# DCDC-5V5V3A.net
KiCad netlist of a schematic drawn in EAGLE
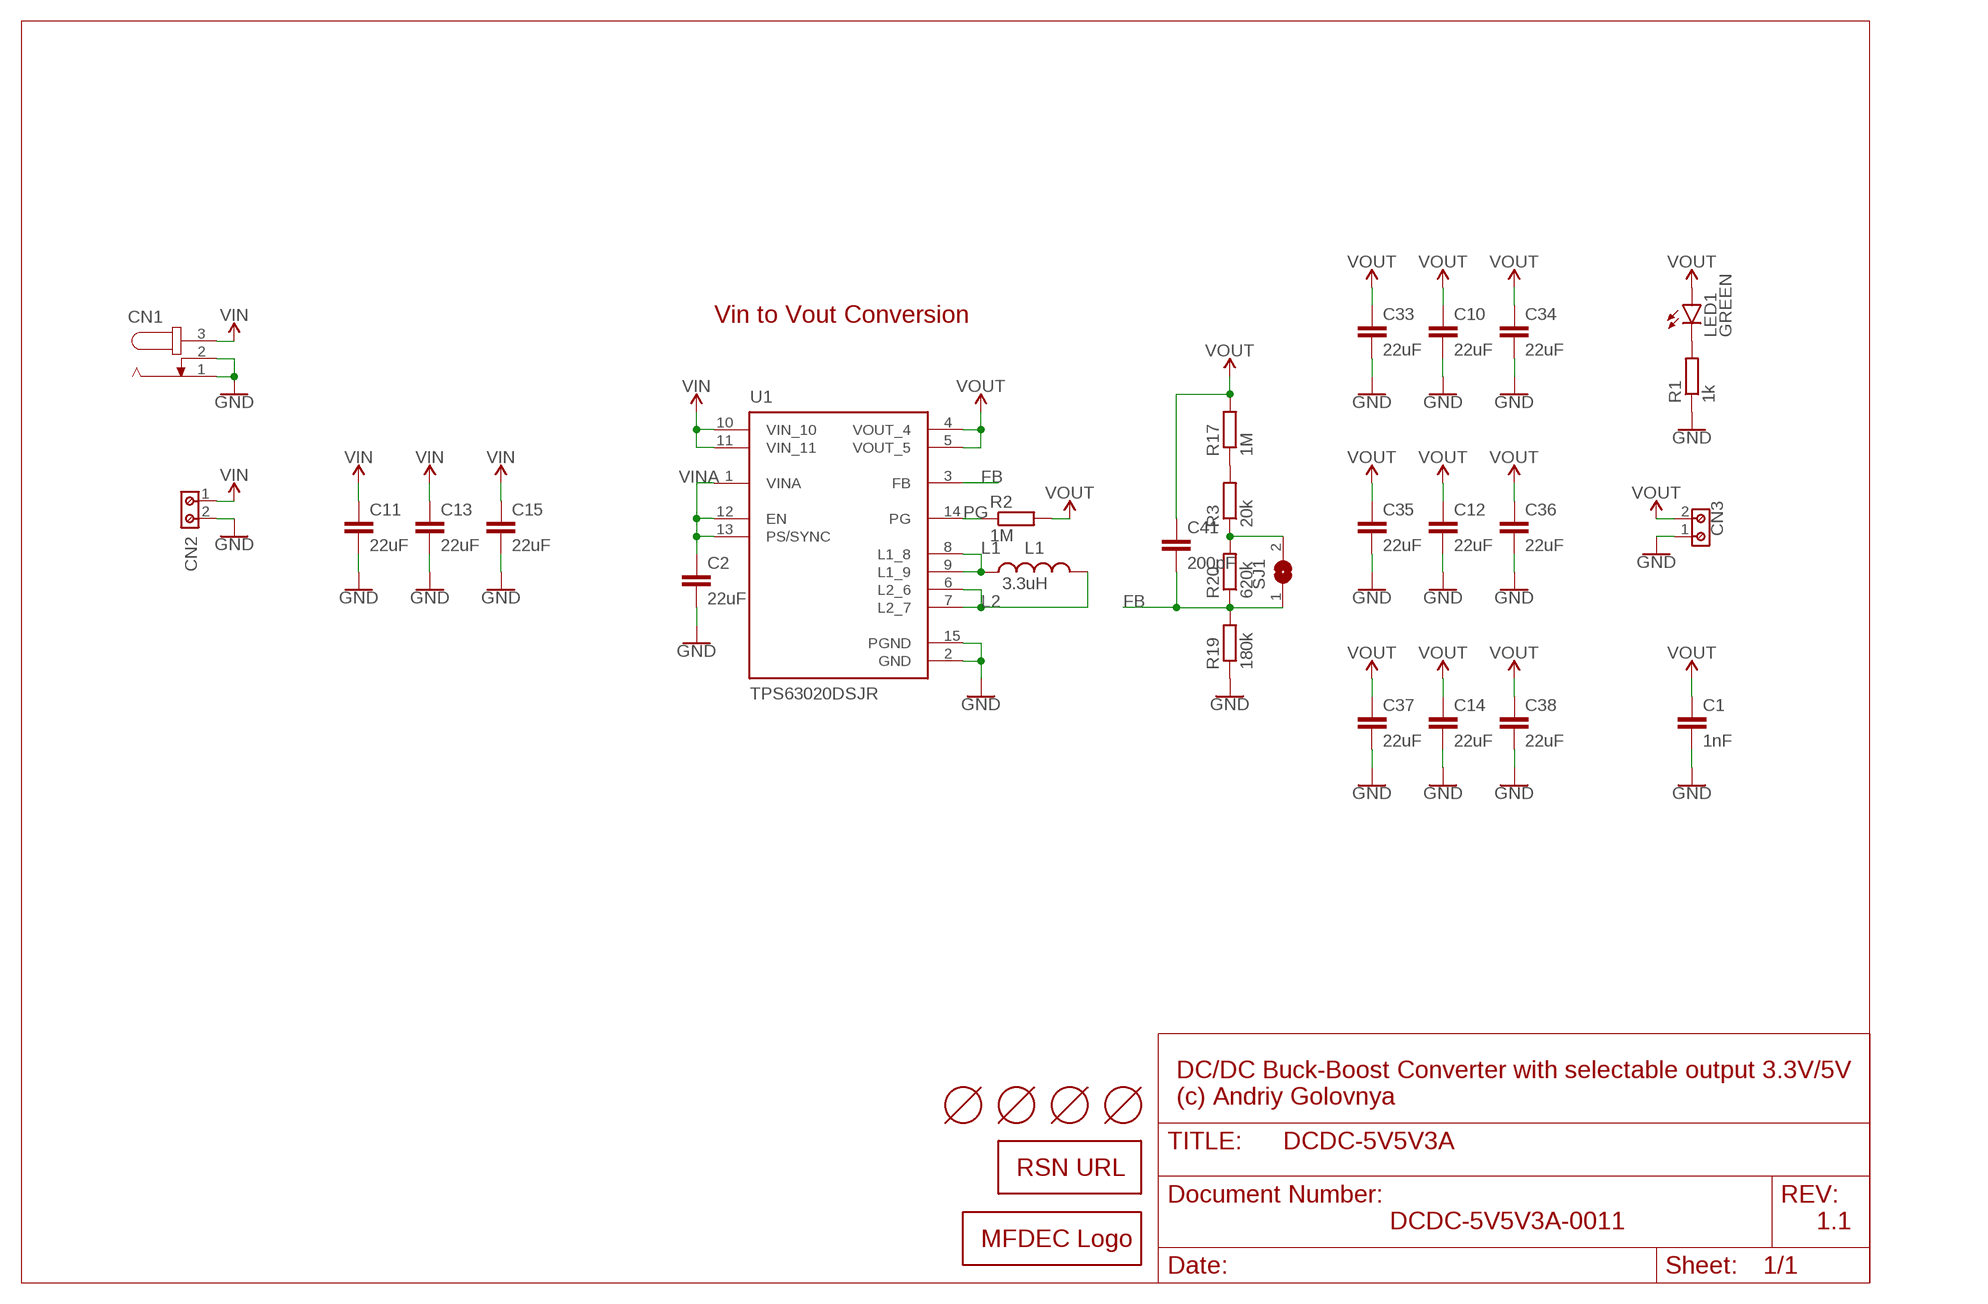
[diagram p0: schematic, sheet 1]

(export (version "E")
  (design (tool "Eeschema 10.0.6"))
  (components
    (comp (ref "C1")
      (value "1nF")
      (footprint "eagle-import:C0603K")
      (libsource (lib "eagle-import") (part "C-EUC0603K"))
    )
    (comp (ref "C2")
      (value "22uF")
      (footprint "eagle-import:C0805K")
      (libsource (lib "eagle-import") (part "C-EUC0805K"))
    )
    (comp (ref "C10")
      (value "22uF")
      (footprint "eagle-import:C0805K")
      (libsource (lib "eagle-import") (part "C-EUC0805K"))
    )
    (comp (ref "C11")
      (value "22uF")
      (footprint "eagle-import:C0805K")
      (libsource (lib "eagle-import") (part "C-EUC0805K"))
    )
    (comp (ref "C12")
      (value "22uF")
      (footprint "eagle-import:C0805K")
      (libsource (lib "eagle-import") (part "C-EUC0805K"))
    )
    (comp (ref "C13")
      (value "22uF")
      (footprint "eagle-import:C0805K")
      (libsource (lib "eagle-import") (part "C-EUC0805K"))
    )
    (comp (ref "C14")
      (value "22uF")
      (footprint "eagle-import:C0805K")
      (libsource (lib "eagle-import") (part "C-EUC0805K"))
    )
    (comp (ref "C15")
      (value "22uF")
      (footprint "eagle-import:C0805K")
      (libsource (lib "eagle-import") (part "C-EUC0805K"))
    )
    (comp (ref "C33")
      (value "22uF")
      (footprint "eagle-import:C0805K")
      (libsource (lib "eagle-import") (part "C-EUC0805K"))
    )
    (comp (ref "C34")
      (value "22uF")
      (footprint "eagle-import:C0805K")
      (libsource (lib "eagle-import") (part "C-EUC0805K"))
    )
    (comp (ref "C35")
      (value "22uF")
      (footprint "eagle-import:C0805K")
      (libsource (lib "eagle-import") (part "C-EUC0805K"))
    )
    (comp (ref "C36")
      (value "22uF")
      (footprint "eagle-import:C0805K")
      (libsource (lib "eagle-import") (part "C-EUC0805K"))
    )
    (comp (ref "C37")
      (value "22uF")
      (footprint "eagle-import:C0805K")
      (libsource (lib "eagle-import") (part "C-EUC0805K"))
    )
    (comp (ref "C38")
      (value "22uF")
      (footprint "eagle-import:C0805K")
      (libsource (lib "eagle-import") (part "C-EUC0805K"))
    )
    (comp (ref "C41")
      (value "200pF")
      (footprint "eagle-import:C0603K")
      (libsource (lib "eagle-import") (part "C-EUC0603K"))
    )
    (comp (ref "CN1")
      (value "JACK-PLUG1")
      (footprint "eagle-import:SPC4078")
      (libsource (lib "eagle-import") (part "JACK-PLUG1"))
    )
    (comp (ref "CN2")
      (value "691213510002")
      (footprint "eagle-import:691213510002")
      (libsource (lib "eagle-import") (part "691213510002"))
    )
    (comp (ref "CN3")
      (value "691213510002")
      (footprint "eagle-import:691213510002")
      (libsource (lib "eagle-import") (part "691213510002"))
    )
    (comp (ref "HOLE1")
      (value "TOOLINGHOLE")
      (footprint "eagle-import:TOOLING-HOLE")
      (libsource (lib "eagle-import") (part "TOOLINGHOLE"))
    )
    (comp (ref "HOLE2")
      (value "TOOLINGHOLE")
      (footprint "eagle-import:TOOLING-HOLE")
      (libsource (lib "eagle-import") (part "TOOLINGHOLE"))
    )
    (comp (ref "HOLE3")
      (value "TOOLINGHOLE")
      (footprint "eagle-import:TOOLING-HOLE")
      (libsource (lib "eagle-import") (part "TOOLINGHOLE"))
    )
    (comp (ref "HOLE4")
      (value "TOOLINGHOLE")
      (footprint "eagle-import:TOOLING-HOLE")
      (libsource (lib "eagle-import") (part "TOOLINGHOLE"))
    )
    (comp (ref "L1")
      (value "3.3uH")
      (footprint "eagle-import:WE-CHSA_1011")
      (libsource (lib "eagle-import") (part "WE-CHSA_1011_7843330330"))
    )
    (comp (ref "LED1")
      (value "GREEN")
      (footprint "eagle-import:SML0603")
      (libsource (lib "eagle-import") (part "LEDSML0603"))
    )
    (comp (ref "LOGO1")
      (value "RSNURL_QR_8MM")
      (footprint "eagle-import:RSNURL_QR_8MM")
      (libsource (lib "eagle-import") (part "RSNURL_QR_8MM"))
    )
    (comp (ref "LOGO2")
      (value "MFDECLOGO_L_10MM")
      (footprint "eagle-import:MFDEC_L_10MM")
      (libsource (lib "eagle-import") (part "MFDECLOGO_L_10MM"))
    )
    (comp (ref "R1")
      (value "1k")
      (footprint "eagle-import:R0603")
      (libsource (lib "eagle-import") (part "R-EU_R0603"))
    )
    (comp (ref "R2")
      (value "1M")
      (footprint "eagle-import:R0603")
      (libsource (lib "eagle-import") (part "R-EU_R0603"))
    )
    (comp (ref "R3")
      (value "20k")
      (footprint "eagle-import:R0603")
      (libsource (lib "eagle-import") (part "R-EU_R0603"))
    )
    (comp (ref "R17")
      (value "1M")
      (footprint "eagle-import:R0603")
      (libsource (lib "eagle-import") (part "R-EU_R0603"))
    )
    (comp (ref "R19")
      (value "180k")
      (footprint "eagle-import:R0603")
      (libsource (lib "eagle-import") (part "R-EU_R0603"))
    )
    (comp (ref "R20")
      (value "620k")
      (footprint "eagle-import:R0603")
      (libsource (lib "eagle-import") (part "R-EU_R0603"))
    )
    (comp (ref "SJ1") (value "SJ") (footprint "eagle-import:SJ") (libsource (lib "eagle-import") (part "SJ")))
    (comp (ref "U1")
      (value "TPS63020DSJR")
      (footprint "eagle-import:IC_TPS63020DSJR")
      (fields (field (name "MF") "Texas Instruments"))
      (libsource (lib "eagle-import") (part "TPS63020DSJR"))
    )
  )
  (nets
    (net (code "1") (name "/FB") (class "Default")
      (node (ref "C41") (pin "2") (pinfunction "2_2") (pintype "passive"))
      (node (ref "R19") (pin "2") (pinfunction "2_2") (pintype "passive"))
      (node (ref "R20") (pin "1") (pinfunction "1_1") (pintype "passive"))
      (node (ref "SJ1") (pin "1") (pinfunction "1_1") (pintype "passive"))
      (node (ref "U1") (pin "3") (pinfunction "FB_3") (pintype "input"))
    )
    (net (code "2") (name "/L1") (class "Default")
      (node (ref "L1") (pin "1") (pinfunction "1_1") (pintype "passive"))
      (node (ref "U1") (pin "8") (pinfunction "L1_8_8") (pintype "passive"))
      (node (ref "U1") (pin "9") (pinfunction "L1_9_9") (pintype "passive"))
    )
    (net (code "3") (name "/L2") (class "Default")
      (node (ref "L1") (pin "2") (pinfunction "2_2") (pintype "passive"))
      (node (ref "U1") (pin "6") (pinfunction "L2_6_6") (pintype "passive"))
      (node (ref "U1") (pin "7") (pinfunction "L2_7_7") (pintype "passive"))
    )
    (net (code "4") (name "/PG") (class "Default")
      (node (ref "R2") (pin "1") (pinfunction "1_1") (pintype "passive"))
      (node (ref "U1") (pin "14") (pinfunction "PG_14") (pintype "output"))
    )
    (net (code "5") (name "/VINA") (class "Default")
      (node (ref "C2") (pin "1") (pinfunction "1_1") (pintype "passive"))
      (node (ref "U1") (pin "1") (pinfunction "VINA_1") (pintype "input"))
      (node (ref "U1") (pin "12") (pinfunction "EN_12") (pintype "input"))
      (node (ref "U1") (pin "13") (pinfunction "PS/SYNC_13") (pintype "input"))
    )
    (net (code "6") (name "GND") (class "Default")
      (node (ref "C1") (pin "2") (pinfunction "2_2") (pintype "passive"))
      (node (ref "C10") (pin "2") (pinfunction "2_2") (pintype "passive"))
      (node (ref "C11") (pin "2") (pinfunction "2_2") (pintype "passive"))
      (node (ref "C12") (pin "2") (pinfunction "2_2") (pintype "passive"))
      (node (ref "C13") (pin "2") (pinfunction "2_2") (pintype "passive"))
      (node (ref "C14") (pin "2") (pinfunction "2_2") (pintype "passive"))
      (node (ref "C15") (pin "2") (pinfunction "2_2") (pintype "passive"))
      (node (ref "C2") (pin "2") (pinfunction "2_2") (pintype "passive"))
      (node (ref "C33") (pin "2") (pinfunction "2_2") (pintype "passive"))
      (node (ref "C34") (pin "2") (pinfunction "2_2") (pintype "passive"))
      (node (ref "C35") (pin "2") (pinfunction "2_2") (pintype "passive"))
      (node (ref "C36") (pin "2") (pinfunction "2_2") (pintype "passive"))
      (node (ref "C37") (pin "2") (pinfunction "2_2") (pintype "passive"))
      (node (ref "C38") (pin "2") (pinfunction "2_2") (pintype "passive"))
      (node (ref "CN1") (pin "1") (pinfunction "1_1") (pintype "passive"))
      (node (ref "CN1") (pin "2") (pinfunction "2_2") (pintype "passive"))
      (node (ref "CN2") (pin "2") (pinfunction "2_2") (pintype "passive"))
      (node (ref "CN3") (pin "1") (pinfunction "1_1") (pintype "passive"))
      (node (ref "R1") (pin "1") (pinfunction "1_1") (pintype "passive"))
      (node (ref "R19") (pin "1") (pinfunction "1_1") (pintype "passive"))
      (node (ref "U1") (pin "15") (pinfunction "PGND_15") (pintype "power_in"))
      (node (ref "U1") (pin "2") (pinfunction "GND_2") (pintype "power_in"))
    )
    (net (code "7") (name "Net-(LED1-PadC)") (class "Default")
      (node (ref "LED1") (pin "C") (pinfunction "C_C") (pintype "passive"))
      (node (ref "R1") (pin "2") (pinfunction "2_2") (pintype "passive"))
    )
    (net (code "8") (name "Net-(R17-Pad1)") (class "Default")
      (node (ref "R17") (pin "1") (pinfunction "1_1") (pintype "passive"))
      (node (ref "R3") (pin "2") (pinfunction "2_2") (pintype "passive"))
    )
    (net (code "9") (name "Net-(R20-Pad2)") (class "Default")
      (node (ref "R20") (pin "2") (pinfunction "2_2") (pintype "passive"))
      (node (ref "R3") (pin "1") (pinfunction "1_1") (pintype "passive"))
      (node (ref "SJ1") (pin "2") (pinfunction "2_2") (pintype "passive"))
    )
    (net (code "10") (name "VIN") (class "Default")
      (node (ref "C11") (pin "1") (pinfunction "1_1") (pintype "passive"))
      (node (ref "C13") (pin "1") (pinfunction "1_1") (pintype "passive"))
      (node (ref "C15") (pin "1") (pinfunction "1_1") (pintype "passive"))
      (node (ref "CN1") (pin "3") (pinfunction "3_3") (pintype "passive"))
      (node (ref "CN2") (pin "1") (pinfunction "1_1") (pintype "passive"))
      (node (ref "U1") (pin "10") (pinfunction "VIN_10_10") (pintype "input"))
      (node (ref "U1") (pin "11") (pinfunction "VIN_11_11") (pintype "input"))
    )
    (net (code "11") (name "VOUT") (class "Default")
      (node (ref "C1") (pin "1") (pinfunction "1_1") (pintype "passive"))
      (node (ref "C10") (pin "1") (pinfunction "1_1") (pintype "passive"))
      (node (ref "C12") (pin "1") (pinfunction "1_1") (pintype "passive"))
      (node (ref "C14") (pin "1") (pinfunction "1_1") (pintype "passive"))
      (node (ref "C33") (pin "1") (pinfunction "1_1") (pintype "passive"))
      (node (ref "C34") (pin "1") (pinfunction "1_1") (pintype "passive"))
      (node (ref "C35") (pin "1") (pinfunction "1_1") (pintype "passive"))
      (node (ref "C36") (pin "1") (pinfunction "1_1") (pintype "passive"))
      (node (ref "C37") (pin "1") (pinfunction "1_1") (pintype "passive"))
      (node (ref "C38") (pin "1") (pinfunction "1_1") (pintype "passive"))
      (node (ref "C41") (pin "1") (pinfunction "1_1") (pintype "passive"))
      (node (ref "CN3") (pin "2") (pinfunction "2_2") (pintype "passive"))
      (node (ref "LED1") (pin "A") (pinfunction "A_A") (pintype "passive"))
      (node (ref "R17") (pin "2") (pinfunction "2_2") (pintype "passive"))
      (node (ref "R2") (pin "2") (pinfunction "2_2") (pintype "passive"))
      (node (ref "U1") (pin "4") (pinfunction "VOUT_4_4") (pintype "output"))
      (node (ref "U1") (pin "5") (pinfunction "VOUT_5_5") (pintype "output"))
    )
  )
)
